# EMG.net
KiCad netlist of a schematic drawn in EAGLE
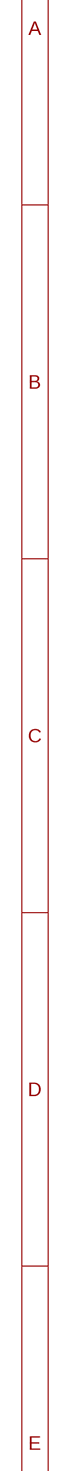
[diagram p0: schematic, sheet 1, part 1 of 2]
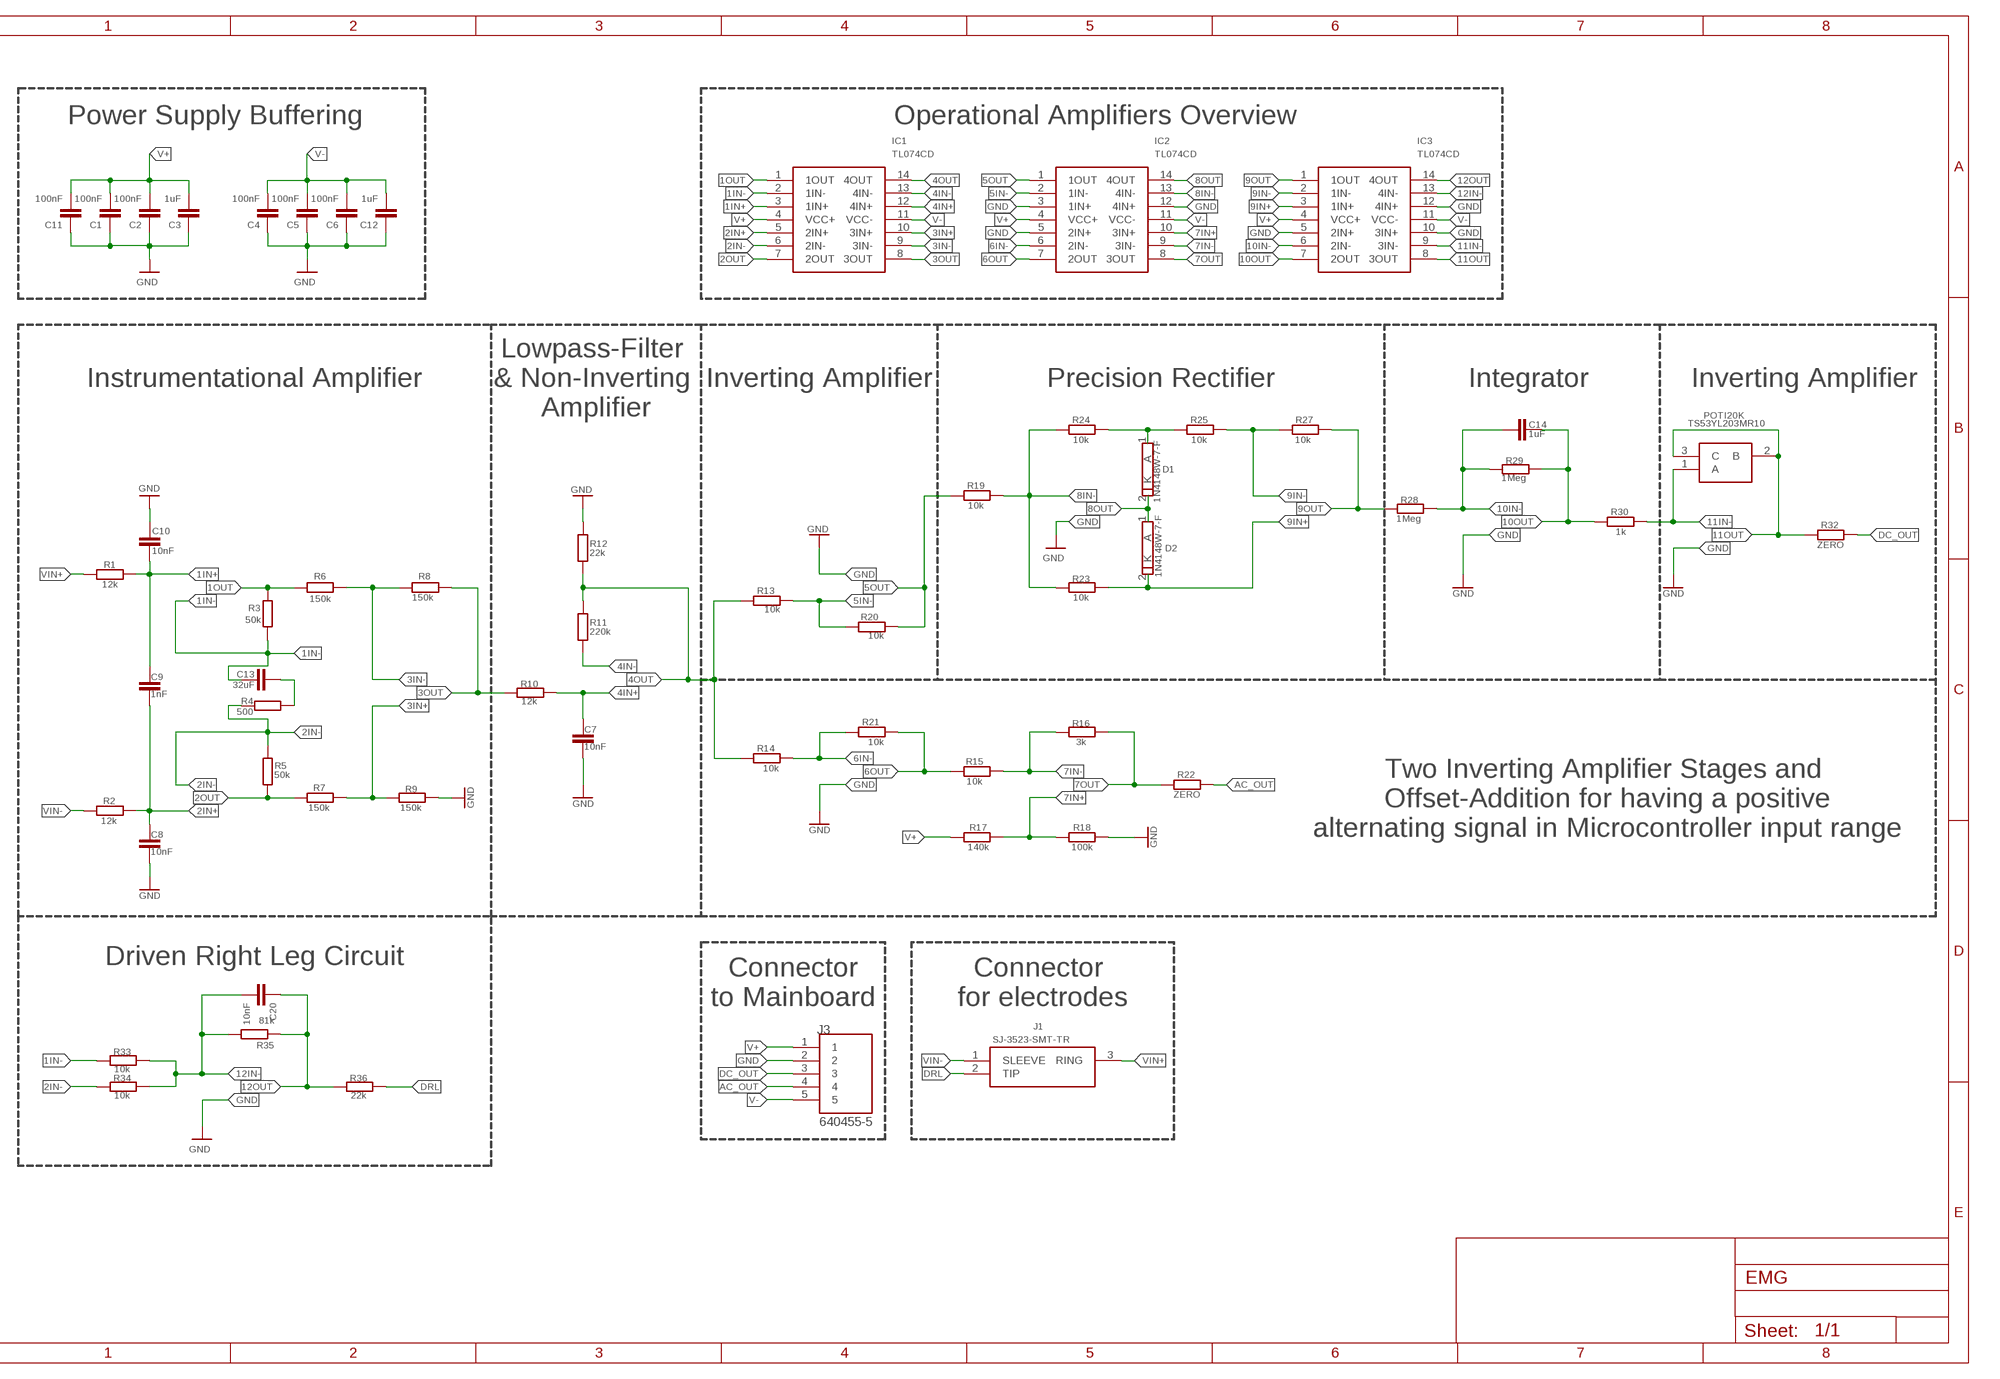
[diagram p1: schematic, sheet 1, part 2 of 2]

(export (version "E")
  (design (tool "Eeschema 10.0.6"))
  (components
    (comp (ref "C1")
      (value "100nF")
      (footprint "eagle-import:C0603")
      (libsource (lib "eagle-import") (part "C-EUC0603"))
    )
    (comp (ref "C2")
      (value "100nF")
      (footprint "eagle-import:C0603")
      (libsource (lib "eagle-import") (part "C-EUC0603"))
    )
    (comp (ref "C3")
      (value "1uF")
      (footprint "eagle-import:C0603")
      (libsource (lib "eagle-import") (part "C-EUC0603"))
    )
    (comp (ref "C4")
      (value "100nF")
      (footprint "eagle-import:C0603")
      (libsource (lib "eagle-import") (part "C-EUC0603"))
    )
    (comp (ref "C5")
      (value "100nF")
      (footprint "eagle-import:C0603")
      (libsource (lib "eagle-import") (part "C-EUC0603"))
    )
    (comp (ref "C6")
      (value "100nF")
      (footprint "eagle-import:C0603")
      (libsource (lib "eagle-import") (part "C-EUC0603"))
    )
    (comp (ref "C7")
      (value "10nF")
      (footprint "eagle-import:C0603")
      (libsource (lib "eagle-import") (part "C-EUC0603"))
    )
    (comp (ref "C8")
      (value "10nF")
      (footprint "eagle-import:C0603")
      (libsource (lib "eagle-import") (part "C-EUC0603"))
    )
    (comp (ref "C9")
      (value "1nF")
      (footprint "eagle-import:C0603")
      (libsource (lib "eagle-import") (part "C-EUC0603"))
    )
    (comp (ref "C10")
      (value "10nF")
      (footprint "eagle-import:C0603")
      (libsource (lib "eagle-import") (part "C-EUC0603"))
    )
    (comp (ref "C11")
      (value "100nF")
      (footprint "eagle-import:C0603")
      (libsource (lib "eagle-import") (part "C-EUC0603"))
    )
    (comp (ref "C12")
      (value "1uF")
      (footprint "eagle-import:C0603")
      (libsource (lib "eagle-import") (part "C-EUC0603"))
    )
    (comp (ref "C13")
      (value "32uF")
      (footprint "eagle-import:C0603")
      (libsource (lib "eagle-import") (part "C-EUC0603"))
    )
    (comp (ref "C14")
      (value "1uF")
      (footprint "eagle-import:C0603")
      (libsource (lib "eagle-import") (part "C-EUC0603"))
    )
    (comp (ref "C20")
      (value "10nF")
      (footprint "eagle-import:C0603")
      (libsource (lib "eagle-import") (part "C-EUC0603"))
    )
    (comp (ref "D1")
      (value "1N4148W-7-F")
      (footprint "eagle-import:SOD3716X115N")
      (fields (field (name "MOUSER_PART_NUMBER") "621-1N4148W-F"))
      (libsource (lib "eagle-import") (part "1N4148W-7-F"))
    )
    (comp (ref "D2")
      (value "1N4148W-7-F")
      (footprint "eagle-import:SOD3716X115N")
      (fields (field (name "MOUSER_PART_NUMBER") "621-1N4148W-F"))
      (libsource (lib "eagle-import") (part "1N4148W-7-F"))
    )
    (comp (ref "IC1")
      (value "TL074CD")
      (footprint "eagle-import:SOIC127P600X175-14N")
      (fields (field (name "MOUSER_PART_NUMBER") "595-TL074CD"))
      (libsource (lib "eagle-import") (part "TL074CD"))
    )
    (comp (ref "IC2")
      (value "TL074CD")
      (footprint "eagle-import:SOIC127P600X175-14N")
      (fields (field (name "MOUSER_PART_NUMBER") "595-TL074CD"))
      (libsource (lib "eagle-import") (part "TL074CD"))
    )
    (comp (ref "IC3")
      (value "TL074CD")
      (footprint "eagle-import:SOIC127P600X175-14N")
      (fields (field (name "MOUSER_PART_NUMBER") "595-TL074CD"))
      (libsource (lib "eagle-import") (part "TL074CD"))
    )
    (comp (ref "J1")
      (value "SJ-3523-SMT-TR")
      (footprint "eagle-import:SJ3523SMTTR")
      (fields (field (name "MOUSER_PART_NUMBER") "490-SJ-3523-SMT-TR"))
      (libsource (lib "eagle-import") (part "SJ-3523-SMT-TR"))
    )
    (comp (ref "J3")
      (value "640455-5")
      (footprint "eagle-import:TE_640455-5")
      (fields (field (name "DIGI-KEY_PART_NUMBER") "A19453-ND") (field (name "MF") "TE Connectivity"))
      (libsource (lib "eagle-import") (part "640455-5"))
    )
    (comp (ref "POTI20K")
      (value "TS53YL203MR10")
      (footprint "eagle-import:TS53YL203MR10")
      (fields (field (name "MOUSER_PART_NUMBER") "72-TS53YL-20K"))
      (libsource (lib "eagle-import") (part "TS53YL203MR10"))
    )
    (comp (ref "R1")
      (value "12k")
      (footprint "eagle-import:R0603")
      (libsource (lib "eagle-import") (part "R-EU_R0603"))
    )
    (comp (ref "R2")
      (value "12k")
      (footprint "eagle-import:R0603")
      (libsource (lib "eagle-import") (part "R-EU_R0603"))
    )
    (comp (ref "R3")
      (value "50k")
      (footprint "eagle-import:R0603")
      (libsource (lib "eagle-import") (part "R-EU_R0603"))
    )
    (comp (ref "R4")
      (value "500")
      (footprint "eagle-import:R0603")
      (libsource (lib "eagle-import") (part "R-EU_R0603"))
    )
    (comp (ref "R5")
      (value "50k")
      (footprint "eagle-import:R0603")
      (libsource (lib "eagle-import") (part "R-EU_R0603"))
    )
    (comp (ref "R6")
      (value "150k")
      (footprint "eagle-import:R0603")
      (libsource (lib "eagle-import") (part "R-EU_R0603"))
    )
    (comp (ref "R7")
      (value "150k")
      (footprint "eagle-import:R0603")
      (libsource (lib "eagle-import") (part "R-EU_R0603"))
    )
    (comp (ref "R8")
      (value "150k")
      (footprint "eagle-import:R0603")
      (libsource (lib "eagle-import") (part "R-EU_R0603"))
    )
    (comp (ref "R9")
      (value "150k")
      (footprint "eagle-import:R0603")
      (libsource (lib "eagle-import") (part "R-EU_R0603"))
    )
    (comp (ref "R10")
      (value "12k")
      (footprint "eagle-import:R0603")
      (libsource (lib "eagle-import") (part "R-EU_R0603"))
    )
    (comp (ref "R11")
      (value "220k")
      (footprint "eagle-import:R0603")
      (libsource (lib "eagle-import") (part "R-EU_R0603"))
    )
    (comp (ref "R12")
      (value "22k")
      (footprint "eagle-import:R0603")
      (libsource (lib "eagle-import") (part "R-EU_R0603"))
    )
    (comp (ref "R13")
      (value "10k")
      (footprint "eagle-import:R0603")
      (libsource (lib "eagle-import") (part "R-EU_R0603"))
    )
    (comp (ref "R14")
      (value "10k")
      (footprint "eagle-import:R0603")
      (libsource (lib "eagle-import") (part "R-EU_R0603"))
    )
    (comp (ref "R15")
      (value "10k")
      (footprint "eagle-import:R0603")
      (libsource (lib "eagle-import") (part "R-EU_R0603"))
    )
    (comp (ref "R16")
      (value "3k")
      (footprint "eagle-import:R0603")
      (libsource (lib "eagle-import") (part "R-EU_R0603"))
    )
    (comp (ref "R17")
      (value "140k")
      (footprint "eagle-import:R0603")
      (libsource (lib "eagle-import") (part "R-EU_R0603"))
    )
    (comp (ref "R18")
      (value "100k")
      (footprint "eagle-import:R0603")
      (libsource (lib "eagle-import") (part "R-EU_R0603"))
    )
    (comp (ref "R19")
      (value "10k")
      (footprint "eagle-import:R0603")
      (libsource (lib "eagle-import") (part "R-EU_R0603"))
    )
    (comp (ref "R20")
      (value "10k")
      (footprint "eagle-import:R0603")
      (libsource (lib "eagle-import") (part "R-EU_R0603"))
    )
    (comp (ref "R21")
      (value "10k")
      (footprint "eagle-import:R0603")
      (libsource (lib "eagle-import") (part "R-EU_R0603"))
    )
    (comp (ref "R22")
      (value "ZERO")
      (footprint "eagle-import:R0603")
      (libsource (lib "eagle-import") (part "R-EU_R0603"))
    )
    (comp (ref "R23")
      (value "10k")
      (footprint "eagle-import:R0603")
      (libsource (lib "eagle-import") (part "R-EU_R0603"))
    )
    (comp (ref "R24")
      (value "10k")
      (footprint "eagle-import:R0603")
      (libsource (lib "eagle-import") (part "R-EU_R0603"))
    )
    (comp (ref "R25")
      (value "10k")
      (footprint "eagle-import:R0603")
      (libsource (lib "eagle-import") (part "R-EU_R0603"))
    )
    (comp (ref "R27")
      (value "10k")
      (footprint "eagle-import:R0603")
      (libsource (lib "eagle-import") (part "R-EU_R0603"))
    )
    (comp (ref "R28")
      (value "1Meg")
      (footprint "eagle-import:R0603")
      (libsource (lib "eagle-import") (part "R-EU_R0603"))
    )
    (comp (ref "R29")
      (value "1Meg")
      (footprint "eagle-import:R0603")
      (libsource (lib "eagle-import") (part "R-EU_R0603"))
    )
    (comp (ref "R30")
      (value "1k")
      (footprint "eagle-import:R0603")
      (libsource (lib "eagle-import") (part "R-EU_R0603"))
    )
    (comp (ref "R32")
      (value "ZERO")
      (footprint "eagle-import:R0603")
      (libsource (lib "eagle-import") (part "R-EU_R0603"))
    )
    (comp (ref "R33")
      (value "10k")
      (footprint "eagle-import:R0603")
      (libsource (lib "eagle-import") (part "R-EU_R0603"))
    )
    (comp (ref "R34")
      (value "10k")
      (footprint "eagle-import:R0603")
      (libsource (lib "eagle-import") (part "R-EU_R0603"))
    )
    (comp (ref "R35")
      (value "81k")
      (footprint "eagle-import:R0603")
      (libsource (lib "eagle-import") (part "R-EU_R0603"))
    )
    (comp (ref "R36")
      (value "22k")
      (footprint "eagle-import:R0603")
      (libsource (lib "eagle-import") (part "R-EU_R0603"))
    )
  )
  (nets
    (net (code "1") (name "1IN+") (class "Default")
      (node (ref "C10") (pin "1") (pinfunction "1_1") (pintype "passive"))
      (node (ref "C9") (pin "1") (pinfunction "1_1") (pintype "passive"))
      (node (ref "IC1") (pin "3") (pinfunction "1IN+_3") (pintype "input"))
      (node (ref "R1") (pin "2") (pinfunction "2_2") (pintype "passive"))
    )
    (net (code "2") (name "1IN-") (class "Default")
      (node (ref "C13") (pin "1") (pinfunction "1_1") (pintype "passive"))
      (node (ref "IC1") (pin "2") (pinfunction "1IN-_2") (pintype "input"))
      (node (ref "R3") (pin "2") (pinfunction "2_2") (pintype "passive"))
      (node (ref "R33") (pin "2") (pinfunction "2_2") (pintype "passive"))
    )
    (net (code "3") (name "1OUT") (class "Default")
      (node (ref "IC1") (pin "1") (pinfunction "1OUT_1") (pintype "output"))
      (node (ref "R3") (pin "1") (pinfunction "1_1") (pintype "passive"))
      (node (ref "R6") (pin "1") (pinfunction "1_1") (pintype "passive"))
    )
    (net (code "4") (name "2IN+") (class "Default")
      (node (ref "C8") (pin "2") (pinfunction "2_2") (pintype "passive"))
      (node (ref "C9") (pin "2") (pinfunction "2_2") (pintype "passive"))
      (node (ref "IC1") (pin "5") (pinfunction "2IN+_5") (pintype "input"))
      (node (ref "R2") (pin "1") (pinfunction "1_1") (pintype "passive"))
    )
    (net (code "5") (name "2IN-") (class "Default")
      (node (ref "IC1") (pin "6") (pinfunction "2IN-_6") (pintype "input"))
      (node (ref "R34") (pin "2") (pinfunction "2_2") (pintype "passive"))
      (node (ref "R4") (pin "2") (pinfunction "2_2") (pintype "passive"))
      (node (ref "R5") (pin "1") (pinfunction "1_1") (pintype "passive"))
    )
    (net (code "6") (name "2OUT") (class "Default")
      (node (ref "IC1") (pin "7") (pinfunction "2OUT_7") (pintype "output"))
      (node (ref "R5") (pin "2") (pinfunction "2_2") (pintype "passive"))
      (node (ref "R7") (pin "2") (pinfunction "2_2") (pintype "passive"))
    )
    (net (code "7") (name "3IN+") (class "Default")
      (node (ref "IC1") (pin "10") (pinfunction "3IN+_10") (pintype "input"))
      (node (ref "R7") (pin "1") (pinfunction "1_1") (pintype "passive"))
      (node (ref "R9") (pin "2") (pinfunction "2_2") (pintype "passive"))
    )
    (net (code "8") (name "3IN-") (class "Default")
      (node (ref "IC1") (pin "9") (pinfunction "3IN-_9") (pintype "input"))
      (node (ref "R6") (pin "2") (pinfunction "2_2") (pintype "passive"))
      (node (ref "R8") (pin "2") (pinfunction "2_2") (pintype "passive"))
    )
    (net (code "9") (name "3OUT") (class "Default")
      (node (ref "IC1") (pin "8") (pinfunction "3OUT_8") (pintype "output"))
      (node (ref "R10") (pin "2") (pinfunction "2_2") (pintype "passive"))
      (node (ref "R8") (pin "1") (pinfunction "1_1") (pintype "passive"))
    )
    (net (code "10") (name "4IN+") (class "Default")
      (node (ref "C7") (pin "2") (pinfunction "2_2") (pintype "passive"))
      (node (ref "IC1") (pin "12") (pinfunction "4IN+_12") (pintype "input"))
      (node (ref "R10") (pin "1") (pinfunction "1_1") (pintype "passive"))
    )
    (net (code "11") (name "4IN-") (class "Default")
      (node (ref "IC1") (pin "13") (pinfunction "4IN-_13") (pintype "input"))
      (node (ref "R11") (pin "2") (pinfunction "2_2") (pintype "passive"))
    )
    (net (code "12") (name "4OUT") (class "Default")
      (node (ref "IC1") (pin "14") (pinfunction "4OUT_14") (pintype "output"))
      (node (ref "R11") (pin "1") (pinfunction "1_1") (pintype "passive"))
      (node (ref "R12") (pin "2") (pinfunction "2_2") (pintype "passive"))
      (node (ref "R13") (pin "2") (pinfunction "2_2") (pintype "passive"))
      (node (ref "R14") (pin "2") (pinfunction "2_2") (pintype "passive"))
    )
    (net (code "13") (name "5IN-") (class "Default")
      (node (ref "IC2") (pin "2") (pinfunction "1IN-_2") (pintype "input"))
      (node (ref "R13") (pin "1") (pinfunction "1_1") (pintype "passive"))
      (node (ref "R20") (pin "2") (pinfunction "2_2") (pintype "passive"))
    )
    (net (code "14") (name "5OUT") (class "Default")
      (node (ref "IC2") (pin "1") (pinfunction "1OUT_1") (pintype "output"))
      (node (ref "R19") (pin "2") (pinfunction "2_2") (pintype "passive"))
      (node (ref "R20") (pin "1") (pinfunction "1_1") (pintype "passive"))
    )
    (net (code "15") (name "6IN-") (class "Default")
      (node (ref "IC2") (pin "6") (pinfunction "2IN-_6") (pintype "input"))
      (node (ref "R14") (pin "1") (pinfunction "1_1") (pintype "passive"))
      (node (ref "R21") (pin "2") (pinfunction "2_2") (pintype "passive"))
    )
    (net (code "16") (name "6OUT") (class "Default")
      (node (ref "IC2") (pin "7") (pinfunction "2OUT_7") (pintype "output"))
      (node (ref "R15") (pin "2") (pinfunction "2_2") (pintype "passive"))
      (node (ref "R21") (pin "1") (pinfunction "1_1") (pintype "passive"))
    )
    (net (code "17") (name "7IN+") (class "Default")
      (node (ref "IC2") (pin "10") (pinfunction "3IN+_10") (pintype "input"))
      (node (ref "R17") (pin "2") (pinfunction "2_2") (pintype "passive"))
      (node (ref "R18") (pin "1") (pinfunction "1_1") (pintype "passive"))
    )
    (net (code "18") (name "7IN-") (class "Default")
      (node (ref "IC2") (pin "9") (pinfunction "3IN-_9") (pintype "input"))
      (node (ref "R15") (pin "1") (pinfunction "1_1") (pintype "passive"))
      (node (ref "R16") (pin "2") (pinfunction "2_2") (pintype "passive"))
    )
    (net (code "19") (name "7OUT") (class "Default")
      (node (ref "IC2") (pin "8") (pinfunction "3OUT_8") (pintype "output"))
      (node (ref "R16") (pin "1") (pinfunction "1_1") (pintype "passive"))
      (node (ref "R22") (pin "2") (pinfunction "2_2") (pintype "passive"))
    )
    (net (code "20") (name "8IN-") (class "Default")
      (node (ref "IC2") (pin "13") (pinfunction "4IN-_13") (pintype "input"))
      (node (ref "R19") (pin "1") (pinfunction "1_1") (pintype "passive"))
      (node (ref "R23") (pin "2") (pinfunction "2_2") (pintype "passive"))
      (node (ref "R24") (pin "2") (pinfunction "2_2") (pintype "passive"))
    )
    (net (code "21") (name "8OUT") (class "Default")
      (node (ref "D1") (pin "2") (pinfunction "K_2") (pintype "bidirectional"))
      (node (ref "D2") (pin "1") (pinfunction "A_1") (pintype "bidirectional"))
      (node (ref "IC2") (pin "14") (pinfunction "4OUT_14") (pintype "output"))
    )
    (net (code "22") (name "9IN+") (class "Default")
      (node (ref "D2") (pin "2") (pinfunction "K_2") (pintype "bidirectional"))
      (node (ref "IC3") (pin "3") (pinfunction "1IN+_3") (pintype "input"))
      (node (ref "R23") (pin "1") (pinfunction "1_1") (pintype "passive"))
    )
    (net (code "23") (name "9IN-") (class "Default")
      (node (ref "IC3") (pin "2") (pinfunction "1IN-_2") (pintype "input"))
      (node (ref "R25") (pin "1") (pinfunction "1_1") (pintype "passive"))
      (node (ref "R27") (pin "2") (pinfunction "2_2") (pintype "passive"))
    )
    (net (code "24") (name "9OUT") (class "Default")
      (node (ref "IC3") (pin "1") (pinfunction "1OUT_1") (pintype "output"))
      (node (ref "R27") (pin "1") (pinfunction "1_1") (pintype "passive"))
      (node (ref "R28") (pin "2") (pinfunction "2_2") (pintype "passive"))
    )
    (net (code "25") (name "10IN-") (class "Default")
      (node (ref "C14") (pin "1") (pinfunction "1_1") (pintype "passive"))
      (node (ref "IC3") (pin "6") (pinfunction "2IN-_6") (pintype "input"))
      (node (ref "R28") (pin "1") (pinfunction "1_1") (pintype "passive"))
      (node (ref "R29") (pin "2") (pinfunction "2_2") (pintype "passive"))
    )
    (net (code "26") (name "10OUT") (class "Default")
      (node (ref "C14") (pin "2") (pinfunction "2_2") (pintype "passive"))
      (node (ref "IC3") (pin "7") (pinfunction "2OUT_7") (pintype "output"))
      (node (ref "R29") (pin "1") (pinfunction "1_1") (pintype "passive"))
      (node (ref "R30") (pin "2") (pinfunction "2_2") (pintype "passive"))
    )
    (net (code "27") (name "11IN-") (class "Default")
      (node (ref "IC3") (pin "9") (pinfunction "3IN-_9") (pintype "input"))
      (node (ref "POTI20K") (pin "1") (pinfunction "A_1") (pintype "bidirectional"))
      (node (ref "R30") (pin "1") (pinfunction "1_1") (pintype "passive"))
    )
    (net (code "28") (name "11OUT") (class "Default")
      (node (ref "IC3") (pin "8") (pinfunction "3OUT_8") (pintype "output"))
      (node (ref "POTI20K") (pin "2") (pinfunction "B_2") (pintype "bidirectional"))
      (node (ref "POTI20K") (pin "3") (pinfunction "C_3") (pintype "bidirectional"))
      (node (ref "R32") (pin "2") (pinfunction "2_2") (pintype "passive"))
    )
    (net (code "29") (name "12IN-") (class "Default")
      (node (ref "C20") (pin "2") (pinfunction "2_2") (pintype "passive"))
      (node (ref "IC3") (pin "13") (pinfunction "4IN-_13") (pintype "input"))
      (node (ref "R33") (pin "1") (pinfunction "1_1") (pintype "passive"))
      (node (ref "R34") (pin "1") (pinfunction "1_1") (pintype "passive"))
      (node (ref "R35") (pin "2") (pinfunction "2_2") (pintype "passive"))
    )
    (net (code "30") (name "12OUT") (class "Default")
      (node (ref "C20") (pin "1") (pinfunction "1_1") (pintype "passive"))
      (node (ref "IC3") (pin "14") (pinfunction "4OUT_14") (pintype "output"))
      (node (ref "R35") (pin "1") (pinfunction "1_1") (pintype "passive"))
      (node (ref "R36") (pin "2") (pinfunction "2_2") (pintype "passive"))
    )
    (net (code "31") (name "AC_OUT") (class "Default")
      (node (ref "J3") (pin "4") (pinfunction "4_4") (pintype "passive"))
      (node (ref "R22") (pin "1") (pinfunction "1_1") (pintype "passive"))
    )
    (net (code "32") (name "DC_OUT") (class "Default")
      (node (ref "J3") (pin "3") (pinfunction "3_3") (pintype "passive"))
      (node (ref "R32") (pin "1") (pinfunction "1_1") (pintype "passive"))
    )
    (net (code "33") (name "DRL") (class "Default")
      (node (ref "J1") (pin "2") (pinfunction "TIP_2") (pintype "bidirectional"))
      (node (ref "R36") (pin "1") (pinfunction "1_1") (pintype "passive"))
    )
    (net (code "34") (name "GND") (class "Default")
      (node (ref "C1") (pin "1") (pinfunction "1_1") (pintype "passive"))
      (node (ref "C10") (pin "2") (pinfunction "2_2") (pintype "passive"))
      (node (ref "C11") (pin "1") (pinfunction "1_1") (pintype "passive"))
      (node (ref "C12") (pin "1") (pinfunction "1_1") (pintype "passive"))
      (node (ref "C2") (pin "1") (pinfunction "1_1") (pintype "passive"))
      (node (ref "C3") (pin "1") (pinfunction "1_1") (pintype "passive"))
      (node (ref "C4") (pin "1") (pinfunction "1_1") (pintype "passive"))
      (node (ref "C5") (pin "1") (pinfunction "1_1") (pintype "passive"))
      (node (ref "C6") (pin "1") (pinfunction "1_1") (pintype "passive"))
      (node (ref "C7") (pin "1") (pinfunction "1_1") (pintype "passive"))
      (node (ref "C8") (pin "1") (pinfunction "1_1") (pintype "passive"))
      (node (ref "IC2") (pin "12") (pinfunction "4IN+_12") (pintype "input"))
      (node (ref "IC2") (pin "3") (pinfunction "1IN+_3") (pintype "input"))
      (node (ref "IC2") (pin "5") (pinfunction "2IN+_5") (pintype "input"))
      (node (ref "IC3") (pin "10") (pinfunction "3IN+_10") (pintype "input"))
      (node (ref "IC3") (pin "12") (pinfunction "4IN+_12") (pintype "input"))
      (node (ref "IC3") (pin "5") (pinfunction "2IN+_5") (pintype "input"))
      (node (ref "J3") (pin "2") (pinfunction "2_2") (pintype "passive"))
      (node (ref "R12") (pin "1") (pinfunction "1_1") (pintype "passive"))
      (node (ref "R18") (pin "2") (pinfunction "2_2") (pintype "passive"))
      (node (ref "R9") (pin "1") (pinfunction "1_1") (pintype "passive"))
    )
    (net (code "35") (name "Net-(C13-Pad2)") (class "Default")
      (node (ref "C13") (pin "2") (pinfunction "2_2") (pintype "passive"))
      (node (ref "R4") (pin "1") (pinfunction "1_1") (pintype "passive"))
    )
    (net (code "36") (name "Net-(D1-A)") (class "Default")
      (node (ref "D1") (pin "1") (pinfunction "A_1") (pintype "bidirectional"))
      (node (ref "R24") (pin "1") (pinfunction "1_1") (pintype "passive"))
      (node (ref "R25") (pin "2") (pinfunction "2_2") (pintype "passive"))
    )
    (net (code "37") (name "V+") (class "Default")
      (node (ref "C1") (pin "2") (pinfunction "2_2") (pintype "passive"))
      (node (ref "C11") (pin "2") (pinfunction "2_2") (pintype "passive"))
      (node (ref "C2") (pin "2") (pinfunction "2_2") (pintype "passive"))
      (node (ref "C3") (pin "2") (pinfunction "2_2") (pintype "passive"))
      (node (ref "IC1") (pin "4") (pinfunction "VCC+_4") (pintype "power_in"))
      (node (ref "IC2") (pin "4") (pinfunction "VCC+_4") (pintype "power_in"))
      (node (ref "IC3") (pin "4") (pinfunction "VCC+_4") (pintype "power_in"))
      (node (ref "J3") (pin "1") (pinfunction "1_1") (pintype "passive"))
      (node (ref "R17") (pin "1") (pinfunction "1_1") (pintype "passive"))
    )
    (net (code "38") (name "V-") (class "Default")
      (node (ref "C12") (pin "2") (pinfunction "2_2") (pintype "passive"))
      (node (ref "C4") (pin "2") (pinfunction "2_2") (pintype "passive"))
      (node (ref "C5") (pin "2") (pinfunction "2_2") (pintype "passive"))
      (node (ref "C6") (pin "2") (pinfunction "2_2") (pintype "passive"))
      (node (ref "IC1") (pin "11") (pinfunction "VCC-_11") (pintype "power_in"))
      (node (ref "IC2") (pin "11") (pinfunction "VCC-_11") (pintype "power_in"))
      (node (ref "IC3") (pin "11") (pinfunction "VCC-_11") (pintype "power_in"))
      (node (ref "J3") (pin "5") (pinfunction "5_5") (pintype "passive"))
    )
    (net (code "39") (name "VIN+") (class "Default")
      (node (ref "J1") (pin "3") (pinfunction "RING_3") (pintype "input"))
      (node (ref "R1") (pin "1") (pinfunction "1_1") (pintype "passive"))
    )
    (net (code "40") (name "VIN-") (class "Default")
      (node (ref "J1") (pin "1") (pinfunction "SLEEVE_1") (pintype "bidirectional"))
      (node (ref "R2") (pin "2") (pinfunction "2_2") (pintype "passive"))
    )
  )
)
